# Dilbert-Badge.net
KiCad netlist of a schematic drawn in EAGLE
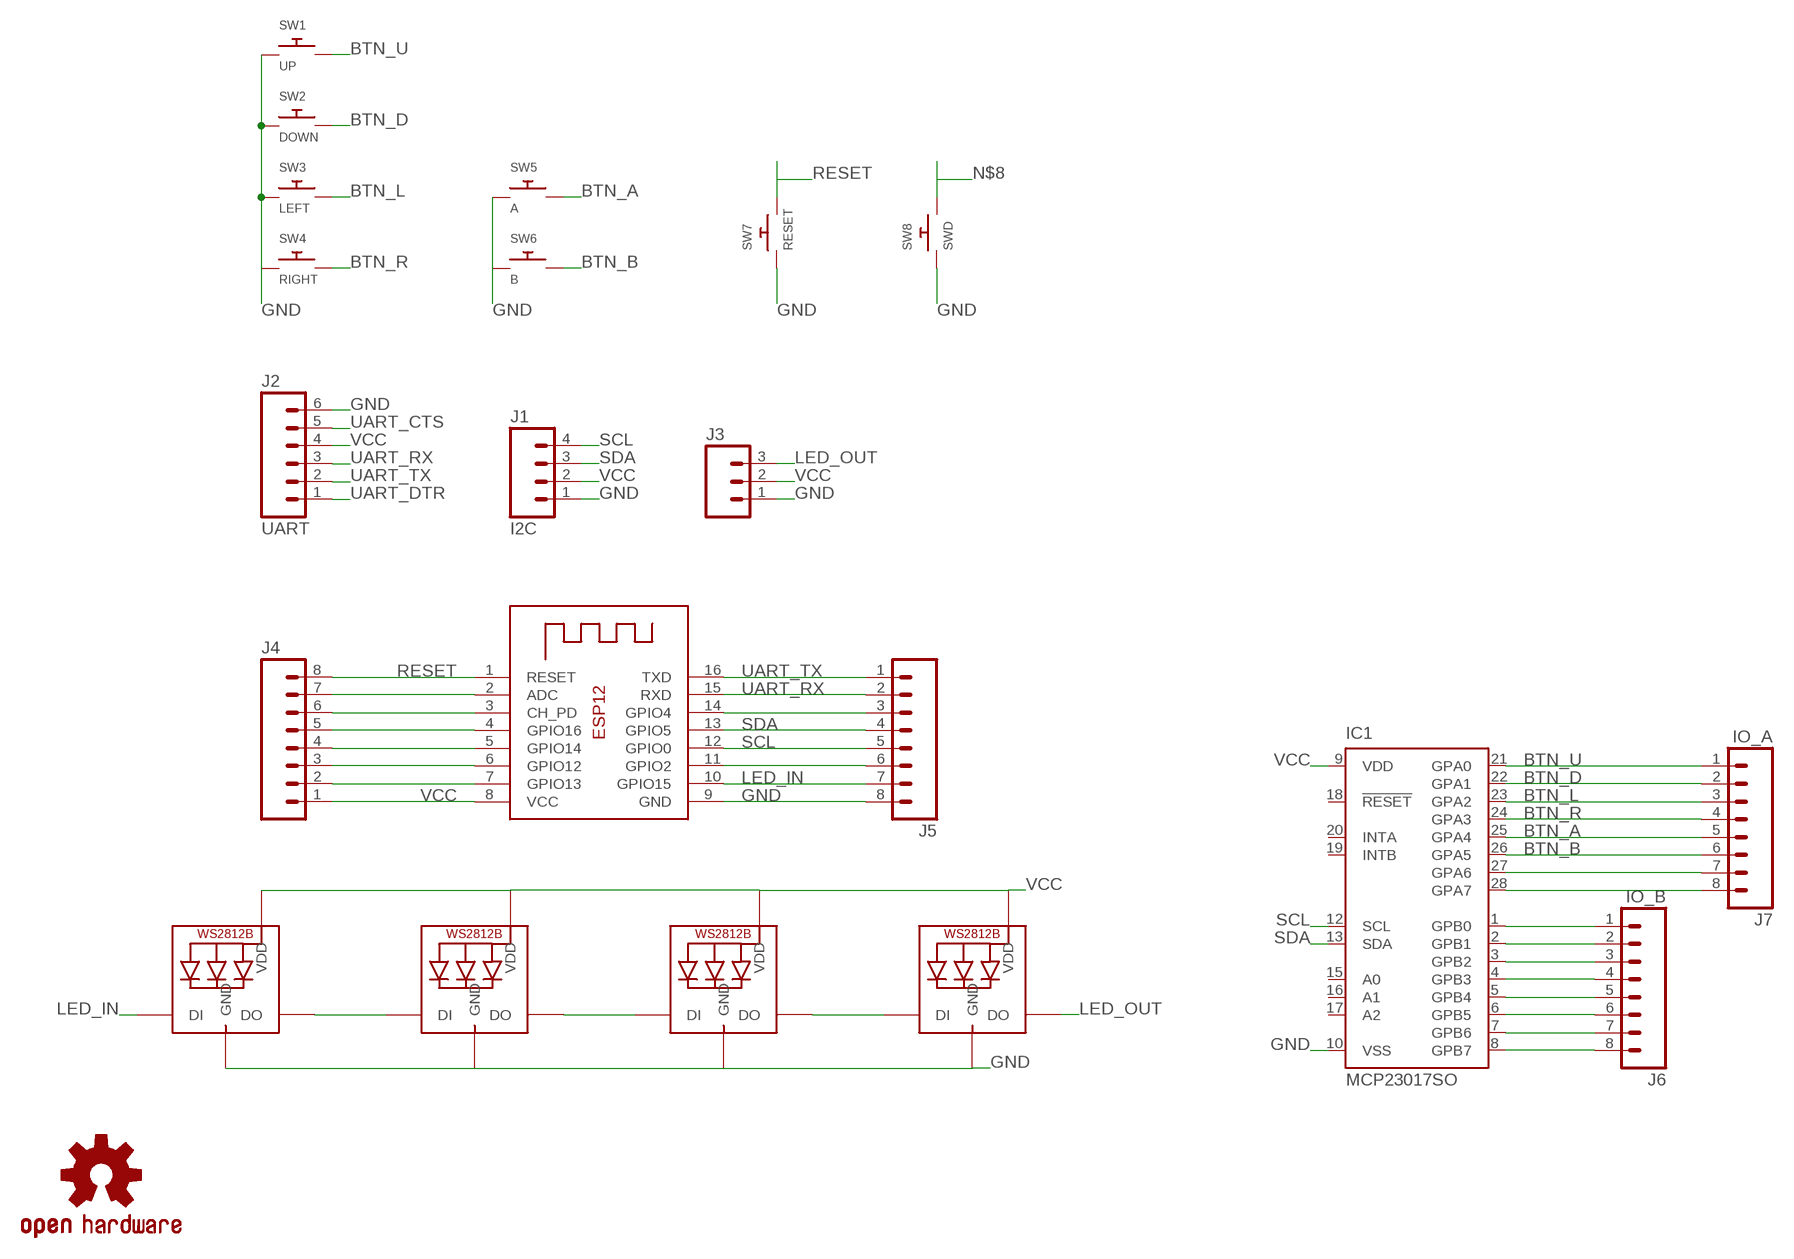
[diagram p0: schematic, sheet 1]

(export (version "E")
  (design (tool "Eeschema 10.0.6"))
  (components
    (comp (ref "IC1")
      (value "MCP23017SO")
      (footprint "eagle-import:SO28W")
      (libsource (lib "eagle-import") (part "MCP23017SO"))
    )
    (comp (ref "J1")
      (value "I2C")
      (footprint "eagle-import:1X04")
      (libsource (lib "eagle-import") (part "M04PTH"))
    )
    (comp (ref "J2")
      (value "UART")
      (footprint "eagle-import:1X06")
      (libsource (lib "eagle-import") (part "M06SILK_FEMALE_PTH"))
    )
    (comp (ref "J3")
      (value "M03PTH")
      (footprint "eagle-import:1X03")
      (libsource (lib "eagle-import") (part "M03PTH"))
    )
    (comp (ref "J4")
      (value "M08NO_SILK_FEMALE_PTH")
      (footprint "eagle-import:1X08_NO_SILK")
      (libsource (lib "eagle-import") (part "M08NO_SILK_FEMALE_PTH"))
    )
    (comp (ref "J5")
      (value "M08NO_SILK_FEMALE_PTH")
      (footprint "eagle-import:1X08_NO_SILK")
      (libsource (lib "eagle-import") (part "M08NO_SILK_FEMALE_PTH"))
    )
    (comp (ref "J6")
      (value "IO_B")
      (footprint "eagle-import:1X08_ROUND")
      (libsource (lib "eagle-import") (part "M08"))
    )
    (comp (ref "J7")
      (value "IO_A")
      (footprint "eagle-import:1X08_ROUND")
      (libsource (lib "eagle-import") (part "M08"))
    )
    (comp (ref "LED1")
      (value "WS2812B5050")
      (footprint "eagle-import:WS2812B")
      (libsource (lib "eagle-import") (part "WS2812B5050"))
    )
    (comp (ref "LED2")
      (value "WS2812B5050")
      (footprint "eagle-import:WS2812B")
      (libsource (lib "eagle-import") (part "WS2812B5050"))
    )
    (comp (ref "LED3")
      (value "WS2812B5050")
      (footprint "eagle-import:WS2812B")
      (libsource (lib "eagle-import") (part "WS2812B5050"))
    )
    (comp (ref "LED4")
      (value "WS2812B5050")
      (footprint "eagle-import:WS2812B")
      (libsource (lib "eagle-import") (part "WS2812B5050"))
    )
    (comp (ref "LOGO1")
      (value "OSHW-LOGOL")
      (footprint "eagle-import:OSHW-LOGO-L")
      (libsource (lib "eagle-import") (part "OSHW-LOGOL"))
    )
    (comp (ref "SW1")
      (value "UP")
      (footprint "eagle-import:TACT_PANA-EVQ")
      (libsource (lib "eagle-import") (part "SWITCH_PUSHBUTTONEVQ-PE"))
    )
    (comp (ref "SW2")
      (value "DOWN")
      (footprint "eagle-import:TACT_PANA-EVQ")
      (libsource (lib "eagle-import") (part "SWITCH_PUSHBUTTONEVQ-PE"))
    )
    (comp (ref "SW3")
      (value "LEFT")
      (footprint "eagle-import:TACT_PANA-EVQ")
      (libsource (lib "eagle-import") (part "SWITCH_PUSHBUTTONEVQ-PE"))
    )
    (comp (ref "SW4")
      (value "RIGHT")
      (footprint "eagle-import:TACT_PANA-EVQ")
      (libsource (lib "eagle-import") (part "SWITCH_PUSHBUTTONEVQ-PE"))
    )
    (comp (ref "SW5")
      (value "A")
      (footprint "eagle-import:TACT_PANA-EVQ")
      (libsource (lib "eagle-import") (part "SWITCH_PUSHBUTTONEVQ-PE"))
    )
    (comp (ref "SW6")
      (value "B")
      (footprint "eagle-import:TACT_PANA-EVQ")
      (libsource (lib "eagle-import") (part "SWITCH_PUSHBUTTONEVQ-PE"))
    )
    (comp (ref "SW7")
      (value "RESET")
      (footprint "eagle-import:TACT_PANA-EVQ")
      (libsource (lib "eagle-import") (part "SWITCH_PUSHBUTTONEVQ-PE"))
    )
    (comp (ref "SW8")
      (value "SWD")
      (footprint "eagle-import:TACT_PANA-EVQ")
      (libsource (lib "eagle-import") (part "SWITCH_PUSHBUTTONEVQ-PE"))
    )
    (comp (ref "X1")
      (value "ESP-12")
      (footprint "eagle-import:ESP-12")
      (libsource (lib "eagle-import") (part "ESP-12"))
    )
  )
  (nets
    (net (code "1") (name "/BTN_A") (class "Default")
      (node (ref "IC1") (pin "25") (pinfunction "GPA4_25") (pintype "bidirectional"))
      (node (ref "J7") (pin "5") (pinfunction "5_5") (pintype "passive"))
      (node (ref "SW5") (pin "P$2") (pinfunction "P$2_P$2") (pintype "passive"))
    )
    (net (code "2") (name "/BTN_B") (class "Default")
      (node (ref "IC1") (pin "26") (pinfunction "GPA5_26") (pintype "bidirectional"))
      (node (ref "J7") (pin "6") (pinfunction "6_6") (pintype "passive"))
      (node (ref "SW6") (pin "P$2") (pinfunction "P$2_P$2") (pintype "passive"))
    )
    (net (code "3") (name "/BTN_D") (class "Default")
      (node (ref "IC1") (pin "22") (pinfunction "GPA1_22") (pintype "bidirectional"))
      (node (ref "J7") (pin "2") (pinfunction "2_2") (pintype "passive"))
      (node (ref "SW2") (pin "P$2") (pinfunction "P$2_P$2") (pintype "passive"))
    )
    (net (code "4") (name "/BTN_L") (class "Default")
      (node (ref "IC1") (pin "23") (pinfunction "GPA2_23") (pintype "bidirectional"))
      (node (ref "J7") (pin "3") (pinfunction "3_3") (pintype "passive"))
      (node (ref "SW3") (pin "P$2") (pinfunction "P$2_P$2") (pintype "passive"))
    )
    (net (code "5") (name "/BTN_R") (class "Default")
      (node (ref "IC1") (pin "24") (pinfunction "GPA3_24") (pintype "bidirectional"))
      (node (ref "J7") (pin "4") (pinfunction "4_4") (pintype "passive"))
      (node (ref "SW4") (pin "P$2") (pinfunction "P$2_P$2") (pintype "passive"))
    )
    (net (code "6") (name "/BTN_U") (class "Default")
      (node (ref "IC1") (pin "21") (pinfunction "GPA0_21") (pintype "bidirectional"))
      (node (ref "J7") (pin "1") (pinfunction "1_1") (pintype "passive"))
      (node (ref "SW1") (pin "P$2") (pinfunction "P$2_P$2") (pintype "passive"))
    )
    (net (code "7") (name "/GND") (class "Default")
      (node (ref "IC1") (pin "10") (pinfunction "VSS_10") (pintype "power_in"))
      (node (ref "J1") (pin "1") (pinfunction "1_1") (pintype "passive"))
      (node (ref "J2") (pin "6") (pinfunction "6_6") (pintype "passive"))
      (node (ref "J3") (pin "1") (pinfunction "1_1") (pintype "passive"))
      (node (ref "J5") (pin "8") (pinfunction "8_8") (pintype "passive"))
      (node (ref "LED1") (pin "3-GND") (pinfunction "GND_3-GND") (pintype "power_in"))
      (node (ref "LED2") (pin "3-GND") (pinfunction "GND_3-GND") (pintype "power_in"))
      (node (ref "LED3") (pin "3-GND") (pinfunction "GND_3-GND") (pintype "power_in"))
      (node (ref "LED4") (pin "3-GND") (pinfunction "GND_3-GND") (pintype "power_in"))
      (node (ref "SW1") (pin "P$1") (pinfunction "P$1_P$1") (pintype "passive"))
      (node (ref "SW2") (pin "P$1") (pinfunction "P$1_P$1") (pintype "passive"))
      (node (ref "SW3") (pin "P$1") (pinfunction "P$1_P$1") (pintype "passive"))
      (node (ref "SW4") (pin "P$1") (pinfunction "P$1_P$1") (pintype "passive"))
      (node (ref "SW5") (pin "P$1") (pinfunction "P$1_P$1") (pintype "passive"))
      (node (ref "SW6") (pin "P$1") (pinfunction "P$1_P$1") (pintype "passive"))
      (node (ref "SW7") (pin "P$1") (pinfunction "P$1_P$1") (pintype "passive"))
      (node (ref "SW8") (pin "P$1") (pinfunction "P$1_P$1") (pintype "passive"))
      (node (ref "X1") (pin "9") (pinfunction "GND_9") (pintype "power_in"))
    )
    (net (code "8") (name "/LED_IN") (class "Default")
      (node (ref "J5") (pin "7") (pinfunction "7_7") (pintype "passive"))
      (node (ref "LED1") (pin "4-DIN") (pinfunction "DI_4-DIN") (pintype "input"))
      (node (ref "X1") (pin "10") (pinfunction "GPIO15_10") (pintype "bidirectional"))
    )
    (net (code "9") (name "/LED_OUT") (class "Default")
      (node (ref "J3") (pin "3") (pinfunction "3_3") (pintype "passive"))
      (node (ref "LED4") (pin "2-DOUT") (pinfunction "DO_2-DOUT") (pintype "output"))
    )
    (net (code "10") (name "/N$8") (class "Default")
      (node (ref "SW8") (pin "P$2") (pinfunction "P$2_P$2") (pintype "passive"))
    )
    (net (code "11") (name "/RESET") (class "Default")
      (node (ref "J4") (pin "8") (pinfunction "8_8") (pintype "passive"))
      (node (ref "SW7") (pin "P$2") (pinfunction "P$2_P$2") (pintype "passive"))
      (node (ref "X1") (pin "1") (pinfunction "RESET_1") (pintype "input"))
    )
    (net (code "12") (name "/SCL") (class "Default")
      (node (ref "IC1") (pin "12") (pinfunction "SCL_12") (pintype "input"))
      (node (ref "J1") (pin "4") (pinfunction "4_4") (pintype "passive"))
      (node (ref "J5") (pin "5") (pinfunction "5_5") (pintype "passive"))
      (node (ref "X1") (pin "12") (pinfunction "GPIO0_12") (pintype "bidirectional"))
    )
    (net (code "13") (name "/SDA") (class "Default")
      (node (ref "IC1") (pin "13") (pinfunction "SDA_13") (pintype "bidirectional"))
      (node (ref "J1") (pin "3") (pinfunction "3_3") (pintype "passive"))
      (node (ref "J5") (pin "4") (pinfunction "4_4") (pintype "passive"))
      (node (ref "X1") (pin "13") (pinfunction "GPIO5_13") (pintype "bidirectional"))
    )
    (net (code "14") (name "/UART_CTS") (class "Default")
      (node (ref "J2") (pin "5") (pinfunction "5_5") (pintype "passive"))
    )
    (net (code "15") (name "/UART_DTR") (class "Default")
      (node (ref "J2") (pin "1") (pinfunction "1_1") (pintype "passive"))
    )
    (net (code "16") (name "/UART_RX") (class "Default")
      (node (ref "J2") (pin "3") (pinfunction "3_3") (pintype "passive"))
      (node (ref "J5") (pin "2") (pinfunction "2_2") (pintype "passive"))
      (node (ref "X1") (pin "15") (pinfunction "RXD_15") (pintype "input"))
    )
    (net (code "17") (name "/UART_TX") (class "Default")
      (node (ref "J2") (pin "2") (pinfunction "2_2") (pintype "passive"))
      (node (ref "J5") (pin "1") (pinfunction "1_1") (pintype "passive"))
      (node (ref "X1") (pin "16") (pinfunction "TXD_16") (pintype "output"))
    )
    (net (code "18") (name "/VCC") (class "Default")
      (node (ref "IC1") (pin "9") (pinfunction "VDD_9") (pintype "power_in"))
      (node (ref "J1") (pin "2") (pinfunction "2_2") (pintype "passive"))
      (node (ref "J2") (pin "4") (pinfunction "4_4") (pintype "passive"))
      (node (ref "J3") (pin "2") (pinfunction "2_2") (pintype "passive"))
      (node (ref "J4") (pin "1") (pinfunction "1_1") (pintype "passive"))
      (node (ref "LED1") (pin "1-VDD") (pinfunction "VDD_1-VDD") (pintype "power_in"))
      (node (ref "LED2") (pin "1-VDD") (pinfunction "VDD_1-VDD") (pintype "power_in"))
      (node (ref "LED3") (pin "1-VDD") (pinfunction "VDD_1-VDD") (pintype "power_in"))
      (node (ref "LED4") (pin "1-VDD") (pinfunction "VDD_1-VDD") (pintype "power_in"))
      (node (ref "X1") (pin "8") (pinfunction "VCC_8") (pintype "power_in"))
    )
    (net (code "19") (name "Net-(IC1-GPA6)") (class "Default")
      (node (ref "IC1") (pin "27") (pinfunction "GPA6_27") (pintype "bidirectional"))
      (node (ref "J7") (pin "7") (pinfunction "7_7") (pintype "passive"))
    )
    (net (code "20") (name "Net-(IC1-GPA7)") (class "Default")
      (node (ref "IC1") (pin "28") (pinfunction "GPA7_28") (pintype "bidirectional"))
      (node (ref "J7") (pin "8") (pinfunction "8_8") (pintype "passive"))
    )
    (net (code "21") (name "Net-(IC1-GPB0)") (class "Default")
      (node (ref "IC1") (pin "1") (pinfunction "GPB0_1") (pintype "bidirectional"))
      (node (ref "J6") (pin "1") (pinfunction "1_1") (pintype "passive"))
    )
    (net (code "22") (name "Net-(IC1-GPB1)") (class "Default")
      (node (ref "IC1") (pin "2") (pinfunction "GPB1_2") (pintype "bidirectional"))
      (node (ref "J6") (pin "2") (pinfunction "2_2") (pintype "passive"))
    )
    (net (code "23") (name "Net-(IC1-GPB2)") (class "Default")
      (node (ref "IC1") (pin "3") (pinfunction "GPB2_3") (pintype "bidirectional"))
      (node (ref "J6") (pin "3") (pinfunction "3_3") (pintype "passive"))
    )
    (net (code "24") (name "Net-(IC1-GPB3)") (class "Default")
      (node (ref "IC1") (pin "4") (pinfunction "GPB3_4") (pintype "bidirectional"))
      (node (ref "J6") (pin "4") (pinfunction "4_4") (pintype "passive"))
    )
    (net (code "25") (name "Net-(IC1-GPB4)") (class "Default")
      (node (ref "IC1") (pin "5") (pinfunction "GPB4_5") (pintype "bidirectional"))
      (node (ref "J6") (pin "5") (pinfunction "5_5") (pintype "passive"))
    )
    (net (code "26") (name "Net-(IC1-GPB5)") (class "Default")
      (node (ref "IC1") (pin "6") (pinfunction "GPB5_6") (pintype "bidirectional"))
      (node (ref "J6") (pin "6") (pinfunction "6_6") (pintype "passive"))
    )
    (net (code "27") (name "Net-(IC1-GPB6)") (class "Default")
      (node (ref "IC1") (pin "7") (pinfunction "GPB6_7") (pintype "bidirectional"))
      (node (ref "J6") (pin "7") (pinfunction "7_7") (pintype "passive"))
    )
    (net (code "28") (name "Net-(IC1-GPB7)") (class "Default")
      (node (ref "IC1") (pin "8") (pinfunction "GPB7_8") (pintype "bidirectional"))
      (node (ref "J6") (pin "8") (pinfunction "8_8") (pintype "passive"))
    )
    (net (code "29") (name "Net-(LED1-DO)") (class "Default")
      (node (ref "LED1") (pin "2-DOUT") (pinfunction "DO_2-DOUT") (pintype "output"))
      (node (ref "LED2") (pin "4-DIN") (pinfunction "DI_4-DIN") (pintype "input"))
    )
    (net (code "30") (name "Net-(LED2-DO)") (class "Default")
      (node (ref "LED2") (pin "2-DOUT") (pinfunction "DO_2-DOUT") (pintype "output"))
      (node (ref "LED3") (pin "4-DIN") (pinfunction "DI_4-DIN") (pintype "input"))
    )
    (net (code "31") (name "Net-(LED3-DO)") (class "Default")
      (node (ref "LED3") (pin "2-DOUT") (pinfunction "DO_2-DOUT") (pintype "output"))
      (node (ref "LED4") (pin "4-DIN") (pinfunction "DI_4-DIN") (pintype "input"))
    )
    (net (code "32") (name "Net-(X1-ADC)") (class "Default")
      (node (ref "J4") (pin "7") (pinfunction "7_7") (pintype "passive"))
      (node (ref "X1") (pin "2") (pinfunction "ADC_2") (pintype "passive"))
    )
    (net (code "33") (name "Net-(X1-CH_PD)") (class "Default")
      (node (ref "J4") (pin "6") (pinfunction "6_6") (pintype "passive"))
      (node (ref "X1") (pin "3") (pinfunction "CH_PD_3") (pintype "input"))
    )
    (net (code "34") (name "Net-(X1-GPIO2)") (class "Default")
      (node (ref "J5") (pin "6") (pinfunction "6_6") (pintype "passive"))
      (node (ref "X1") (pin "11") (pinfunction "GPIO2_11") (pintype "bidirectional"))
    )
    (net (code "35") (name "Net-(X1-GPIO4)") (class "Default")
      (node (ref "J5") (pin "3") (pinfunction "3_3") (pintype "passive"))
      (node (ref "X1") (pin "14") (pinfunction "GPIO4_14") (pintype "bidirectional"))
    )
    (net (code "36") (name "Net-(X1-GPIO12)") (class "Default")
      (node (ref "J4") (pin "3") (pinfunction "3_3") (pintype "passive"))
      (node (ref "X1") (pin "6") (pinfunction "GPIO12_6") (pintype "bidirectional"))
    )
    (net (code "37") (name "Net-(X1-GPIO13)") (class "Default")
      (node (ref "J4") (pin "2") (pinfunction "2_2") (pintype "passive"))
      (node (ref "X1") (pin "7") (pinfunction "GPIO13_7") (pintype "bidirectional"))
    )
    (net (code "38") (name "Net-(X1-GPIO14)") (class "Default")
      (node (ref "J4") (pin "4") (pinfunction "4_4") (pintype "passive"))
      (node (ref "X1") (pin "5") (pinfunction "GPIO14_5") (pintype "bidirectional"))
    )
    (net (code "39") (name "Net-(X1-GPIO16)") (class "Default")
      (node (ref "J4") (pin "5") (pinfunction "5_5") (pintype "passive"))
      (node (ref "X1") (pin "4") (pinfunction "GPIO16_4") (pintype "bidirectional"))
    )
    (net (code "40") (name "unconnected-(IC1-A0-Pad15)") (class "Default")
      (node (ref "IC1") (pin "15") (pinfunction "A0_15") (pintype "input"))
    )
    (net (code "41") (name "unconnected-(IC1-A1-Pad16)") (class "Default")
      (node (ref "IC1") (pin "16") (pinfunction "A1_16") (pintype "input"))
    )
    (net (code "42") (name "unconnected-(IC1-A2-Pad17)") (class "Default")
      (node (ref "IC1") (pin "17") (pinfunction "A2_17") (pintype "input"))
    )
    (net (code "43") (name "unconnected-(IC1-INTA-Pad20)") (class "Default")
      (node (ref "IC1") (pin "20") (pinfunction "INTA_20") (pintype "output"))
    )
    (net (code "44") (name "unconnected-(IC1-INTB-Pad19)") (class "Default")
      (node (ref "IC1") (pin "19") (pinfunction "INTB_19") (pintype "output"))
    )
    (net (code "45") (name "unconnected-(IC1-~{RESET}-Pad18)") (class "Default")
      (node (ref "IC1") (pin "18") (pinfunction "~{RESET}_18") (pintype "input"))
    )
  )
)
